# Crawler_Power_V2_0.net
KiCad netlist of a schematic drawn in Altium Designer
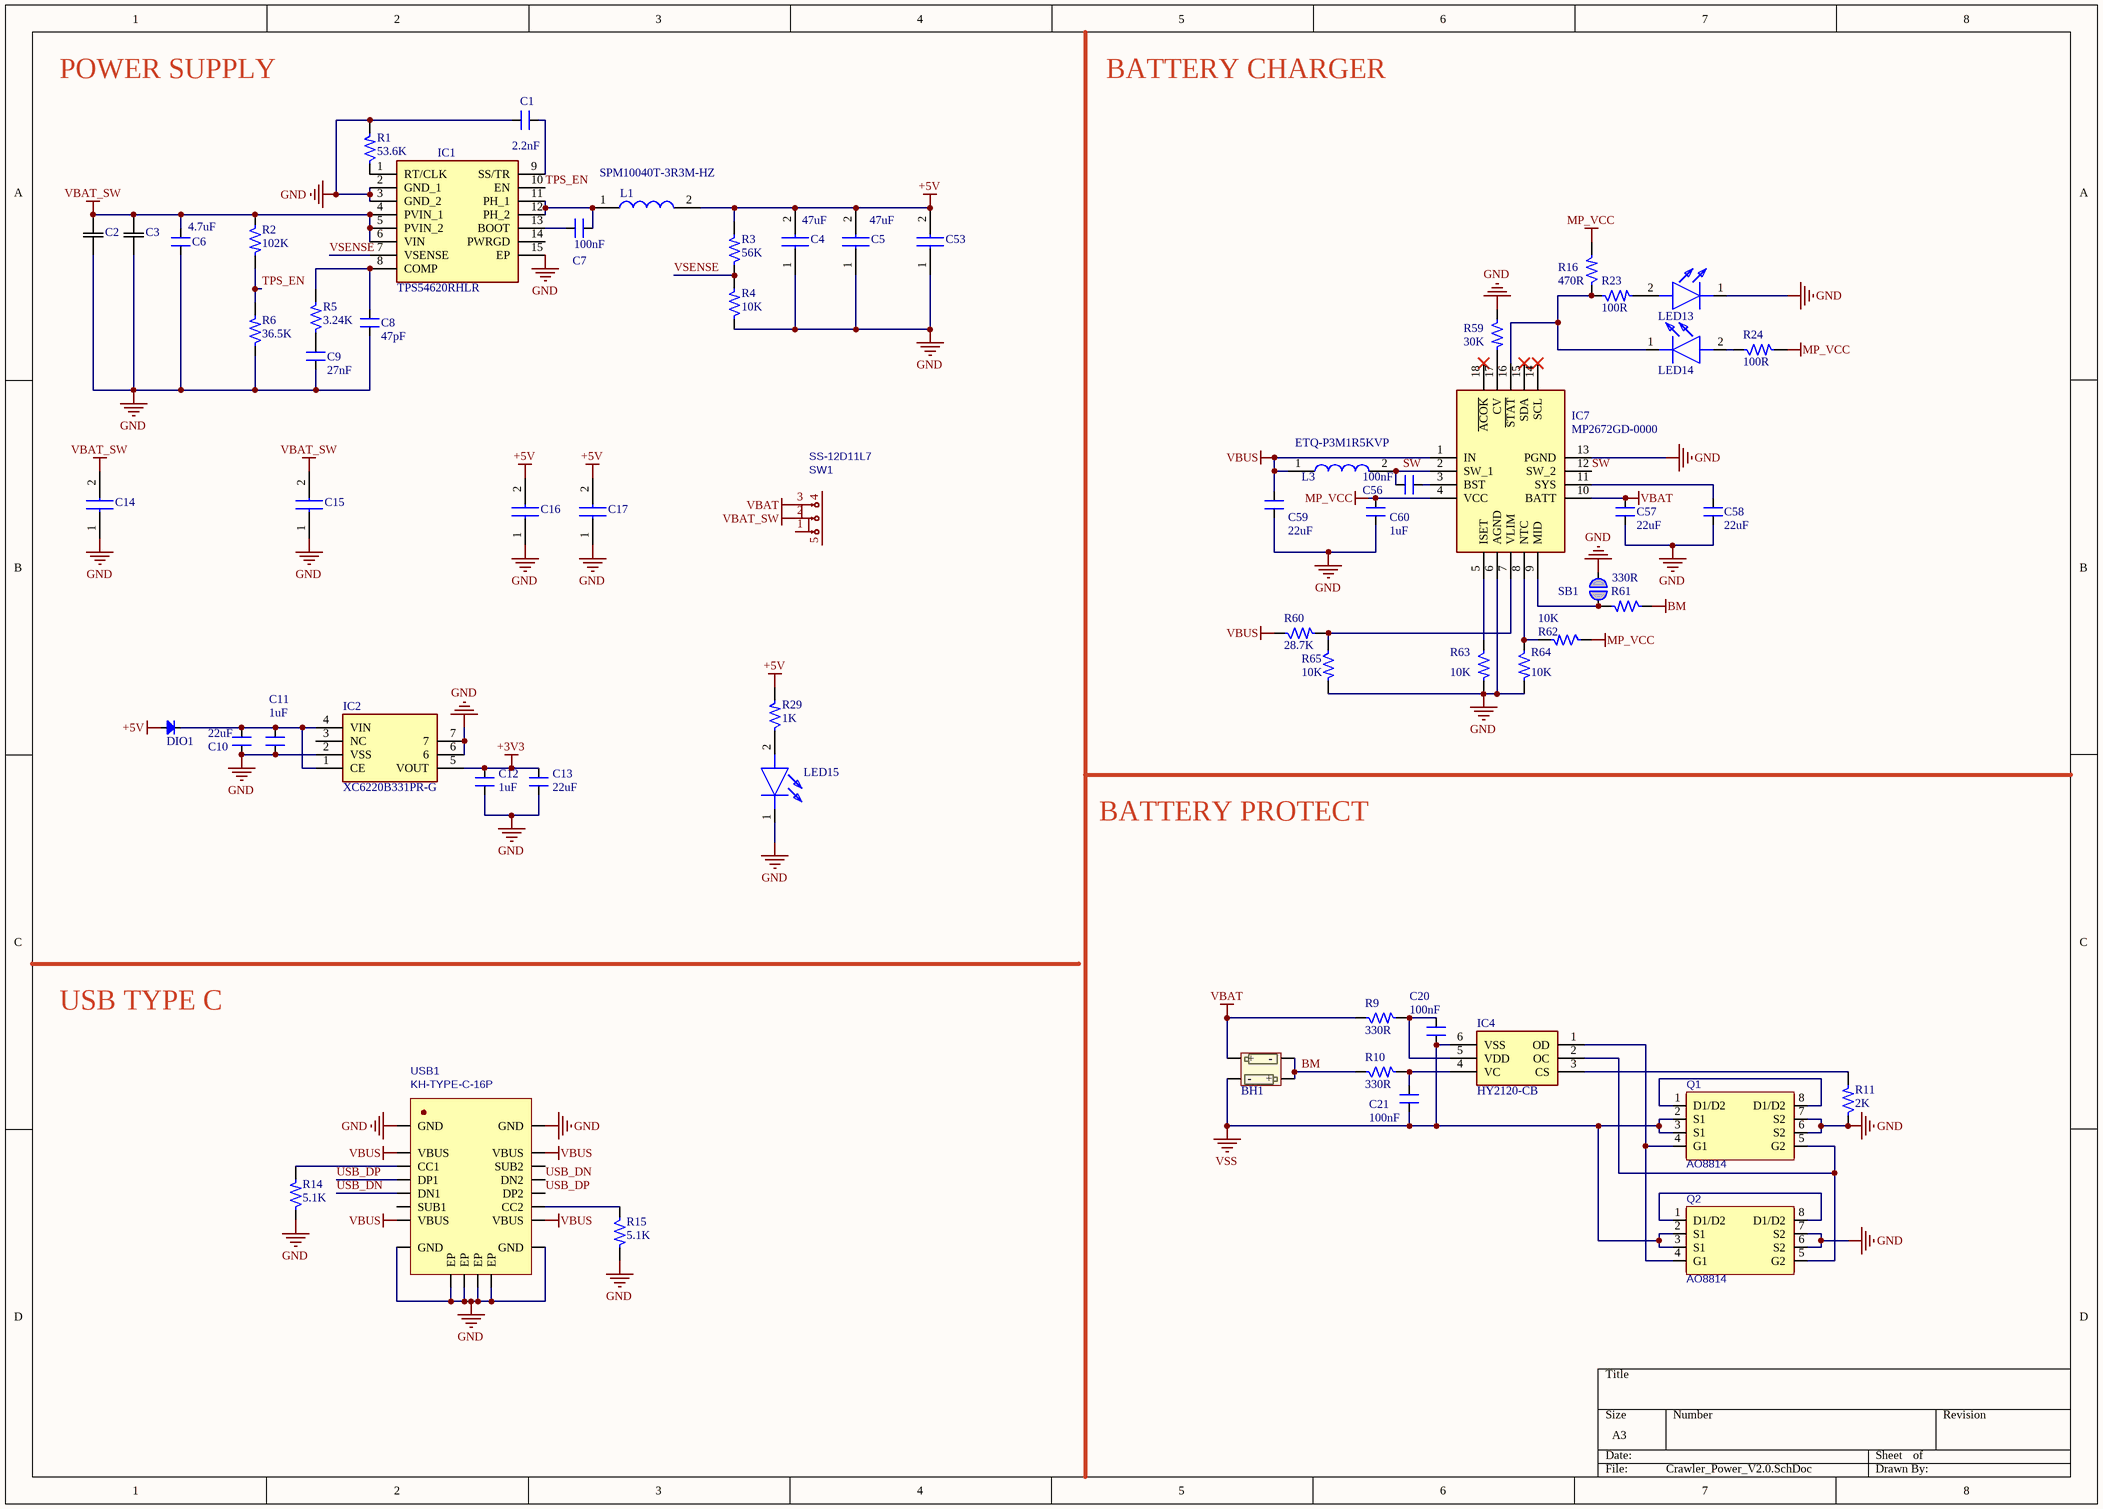
[diagram p0: Crawler_Power_V2.0.SchDoc]

(export (version "E")
  (design (tool "Eeschema 10.0.6"))
  (components
    (comp (ref "BH1")
      (value "Battery Holder")
      (footprint "BH-18650-B1BA007")
      (libsource (lib "SamacSys") (part "BH-18650-B1BA007"))
    )
    (comp (ref "C1")
      (value "2.2nF")
      (footprint "CAP_0402")
      (description "2.2nF ±10% 50V Ceramic Capacitor X7R 0402 (1005 Metric)")
      (fields
        (field (name "MANUFACTURER") "KEMET")
        (field (name "MANUFACTURER PART NUMBER") "C0402C221K8RAC7867")
      )
      (libsource (lib "EsteemPCB_SOM_Course_schlib") (part "CAP_220pF-10V-10%-0402"))
    )
    (comp (ref "C2")
      (value "CC1206MKX5R7BB106")
      (footprint "CAP_CC1206_YAG-M")
      (description "No Description Available")
      (fields (field (name "COPYRIGHT") "Copyright (C) 2023 Ultra Librarian. All rights reserved."))
      (libsource (lib "SamacSys") (part "CC1206MKX5R7BB106"))
    )
    (comp (ref "C3")
      (value "CC1206MKX5R7BB106")
      (footprint "CAP_CC1206_YAG-M")
      (description "No Description Available")
      (fields (field (name "COPYRIGHT") "Copyright (C) 2023 Ultra Librarian. All rights reserved."))
      (libsource (lib "SamacSys") (part "CC1206MKX5R7BB106"))
    )
    (comp (ref "C4")
      (value "GRM32ER61C476KE15L")
      (footprint "CAPC3225X270N")
      (description "Capacitor")
      (fields (field (name "MOUSER PART NUMBER") "81-GRM32ER61C476KE5L"))
      (libsource (lib "SamacSys") (part "GRM32ER61C476KE15L"))
    )
    (comp (ref "C5")
      (value "GRM32ER61C476KE15L")
      (footprint "CAPC3225X270N")
      (description "Capacitor")
      (fields (field (name "MOUSER PART NUMBER") "81-GRM32ER61C476KE5L"))
      (libsource (lib "SamacSys") (part "GRM32ER61C476KE15L"))
    )
    (comp (ref "C6")
      (value "4.7uF")
      (footprint "CAP_0402")
      (description "4.7µF ±10% 10V Ceramic Capacitor X5R 0402 (1005 Metric)")
      (fields
        (field (name "MANUFACTURER") "Samsung Electro-Mechanics")
        (field (name "MANUFACTURER PART NUMBER") "CL05A475KP5NRNC")
      )
      (libsource (lib "EsteemPCB_SOM_Course_schlib") (part "CAP_4.7uF-10V-10%-0402"))
    )
    (comp (ref "C7")
      (value "100nF")
      (footprint "CAP_0603")
      (description "25V 100nF X7R ±10% 0603 Multilayer Ceramic Capacitors MLCC - SMD/SMT ROHS")
      (fields
        (field (name "MANUFACTURER") "Yageo")
        (field (name "MANUFACTURER PART NUMBER") "CC0603KRX7R6BB104")
      )
      (libsource (lib "EsteemPCB_SOM_Course_schlib") (part "CAP_100nF-10V-5%-0603"))
    )
    (comp (ref "C8")
      (value "47pF")
      (footprint "CAP_0402")
      (description "82pF ±10% 50V Ceramic Capacitor NP0 0402 (1005 Metric)")
      (fields
        (field (name "MANUFACTURER") "KEMET")
        (field (name "MANUFACTURER PART NUMBER") "C0402C221K8RAC7867")
      )
      (libsource (lib "EsteemPCB_SOM_Course_schlib") (part "CAP_220pF-10V-10%-0402"))
    )
    (comp (ref "C9")
      (value "27nF")
      (footprint "CAP_0402")
      (description "27nF ±10% 50V Ceramic Capacitor X7R 0402 (1005 Metric)")
      (fields
        (field (name "MANUFACTURER") "KEMET")
        (field (name "MANUFACTURER PART NUMBER") "C0402C221K8RAC7867")
      )
      (libsource (lib "EsteemPCB_SOM_Course_schlib") (part "CAP_220pF-10V-10%-0402"))
    )
    (comp (ref "C10")
      (value "22uF")
      (footprint "CAP_0603")
      (description "22µF ±20% 10V Ceramic Capacitor X5R 0603 (1608 Metric)")
      (fields
        (field (name "MANUFACTURER") "Murata Electronics")
        (field (name "MANUFACTURER PART NUMBER") "GRM188R61A226ME15D")
      )
      (libsource (lib "EsteemPCB_SOM_Course_schlib") (part "CAP_22uF-10V-20%-0603"))
    )
    (comp (ref "C11")
      (value "1uF")
      (footprint "CAP_0402")
      (description "1µF ±10% 10V Ceramic Capacitor X6S 0402 (1005 Metric)")
      (fields
        (field (name "MANUFACTURER") "Murata Electronics")
        (field (name "MANUFACTURER PART NUMBER") "GRT155C81A105KE01D")
      )
      (libsource (lib "EsteemPCB_SOM_Course_schlib") (part "CAP_1uF-10V-10%-0402"))
    )
    (comp (ref "C12")
      (value "1uF")
      (footprint "CAP_0402")
      (description "1µF ±10% 10V Ceramic Capacitor X6S 0402 (1005 Metric)")
      (fields
        (field (name "MANUFACTURER") "Murata Electronics")
        (field (name "MANUFACTURER PART NUMBER") "GRT155C81A105KE01D")
      )
      (libsource (lib "EsteemPCB_SOM_Course_schlib") (part "CAP_1uF-10V-10%-0402"))
    )
    (comp (ref "C13")
      (value "22uF")
      (footprint "CAP_0603")
      (description "22µF ±20% 10V Ceramic Capacitor X5R 0603 (1608 Metric)")
      (fields
        (field (name "MANUFACTURER") "Murata Electronics")
        (field (name "MANUFACTURER PART NUMBER") "GRM188R61A226ME15D")
      )
      (libsource (lib "EsteemPCB_SOM_Course_schlib") (part "CAP_22uF-10V-20%-0603"))
    )
    (comp (ref "C14")
      (value "GRM32ER61C476KE15L")
      (footprint "CAPC3225X270N")
      (description "Capacitor")
      (fields (field (name "MOUSER PART NUMBER") "81-GRM32ER61C476KE5L"))
      (libsource (lib "SamacSys") (part "GRM32ER61C476KE15L"))
    )
    (comp (ref "C15")
      (value "GRM32ER61C476KE15L")
      (footprint "CAPC3225X270N")
      (description "Capacitor")
      (fields (field (name "MOUSER PART NUMBER") "81-GRM32ER61C476KE5L"))
      (libsource (lib "SamacSys") (part "GRM32ER61C476KE15L"))
    )
    (comp (ref "C16")
      (value "GRM32ER61C476KE15L")
      (footprint "CAPC3225X270N")
      (description "Capacitor")
      (fields (field (name "MOUSER PART NUMBER") "81-GRM32ER61C476KE5L"))
      (libsource (lib "SamacSys") (part "GRM32ER61C476KE15L"))
    )
    (comp (ref "C17")
      (value "GRM32ER61C476KE15L")
      (footprint "CAPC3225X270N")
      (description "Capacitor")
      (fields (field (name "MOUSER PART NUMBER") "81-GRM32ER61C476KE5L"))
      (libsource (lib "SamacSys") (part "GRM32ER61C476KE15L"))
    )
    (comp (ref "C20")
      (value "100nF")
      (footprint "CAP_0402")
      (description "0.1µF ±10% 25V Ceramic Capacitor X7R 0402 (1005 Metric)")
      (fields
        (field (name "MANUFACTURER") "Walsin Technology Corporation")
        (field (name "MANUFACTURER PART NUMBER") "0402B104K250CT")
      )
      (libsource (lib "EsteemPCB_SOM_Course_schlib") (part "CAP_100nF-25V-10%-0402"))
    )
    (comp (ref "C21")
      (value "100nF")
      (footprint "CAP_0402")
      (description "0.1µF ±10% 25V Ceramic Capacitor X7R 0402 (1005 Metric)")
      (fields
        (field (name "MANUFACTURER") "Walsin Technology Corporation")
        (field (name "MANUFACTURER PART NUMBER") "0402B104K250CT")
      )
      (libsource (lib "EsteemPCB_SOM_Course_schlib") (part "CAP_100nF-25V-10%-0402"))
    )
    (comp (ref "C53")
      (value "GRM32ER61C476KE15L")
      (footprint "CAPC3225X270N")
      (description "Capacitor")
      (fields (field (name "MOUSER PART NUMBER") "81-GRM32ER61C476KE5L"))
      (libsource (lib "SamacSys") (part "GRM32ER61C476KE15L"))
    )
    (comp (ref "C56")
      (value "100nF")
      (footprint "CAP_0603")
      (description "25V 100nF X7R ±10% 0603 Multilayer Ceramic Capacitors MLCC - SMD/SMT ROHS")
      (fields
        (field (name "MANUFACTURER") "Yageo")
        (field (name "MANUFACTURER PART NUMBER") "CC0603KRX7R6BB104")
      )
      (libsource (lib "EsteemPCB_SOM_Course_schlib") (part "CAP_100nF-10V-5%-0603"))
    )
    (comp (ref "C57")
      (value "22uF")
      (footprint "CAP_0805")
      (description "22µF ±20% 25V Ceramic Capacitor X5R 0805 (2012 Metric)")
      (fields
        (field (name "MANUFACTURER") "Murata Electronics")
        (field (name "MANUFACTURER PART NUMBER") "GRM21BR61E226ME44K")
      )
      (libsource (lib "EsteemPCB_SOM_Course_schlib") (part "CAP_22uF-25V-20%-0805"))
    )
    (comp (ref "C58")
      (value "22uF")
      (footprint "CAP_0805")
      (description "22µF ±20% 25V Ceramic Capacitor X5R 0805 (2012 Metric)")
      (fields
        (field (name "MANUFACTURER") "Murata Electronics")
        (field (name "MANUFACTURER PART NUMBER") "GRM21BR61E226ME44K")
      )
      (libsource (lib "EsteemPCB_SOM_Course_schlib") (part "CAP_22uF-25V-20%-0805"))
    )
    (comp (ref "C59")
      (value "22uF")
      (footprint "CAP_0603")
      (description "22µF ±20% 10V Ceramic Capacitor X5R 0603 (1608 Metric)")
      (fields
        (field (name "MANUFACTURER") "Murata Electronics")
        (field (name "MANUFACTURER PART NUMBER") "GRM188R61A226ME15D")
      )
      (libsource (lib "EsteemPCB_SOM_Course_schlib") (part "CAP_22uF-10V-20%-0603"))
    )
    (comp (ref "C60")
      (value "1uF")
      (footprint "CAP_0402")
      (description "1µF ±10% 10V Ceramic Capacitor X6S 0402 (1005 Metric)")
      (fields
        (field (name "MANUFACTURER") "Murata Electronics")
        (field (name "MANUFACTURER PART NUMBER") "GRT155C81A105KE01D")
      )
      (libsource (lib "EsteemPCB_SOM_Course_schlib") (part "CAP_1uF-10V-10%-0402"))
    )
    (comp (ref "DIO1")
      (value "Diode SMD")
      (footprint "DIO-SMD-123")
      (description "Default Diode")
      (fields (field (name "PUBLISHER") "Altium Limited"))
      (libsource (lib "LIBRARY") (part "Diode SMD"))
    )
    (comp (ref "IC1")
      (value "TPS54620RHLR")
      (footprint "SamacSys:TPS54622RHLR")
      (description "Integrated Circuit")
      (fields (field (name "MOUSER PART NUMBER") "595-TPS54620RHLR"))
      (libsource (lib "*") (part "TPS54620RHLR"))
    )
    (comp (ref "IC2")
      (value "XC6220B331PR-G")
      (footprint "XC6220B331PRG")
      (description "Integrated Circuit")
      (fields (field (name "MOUSER PART NUMBER") "865-XC6220B331PR-G"))
      (libsource (lib "*") (part "XC6220B331PR-G"))
    )
    (comp (ref "IC4")
      (value "HY2120-CB")
      (footprint "SamacSys:SOT95P280X140-6N")
      (description "Integrated Circuit")
      (libsource (lib "*") (part "HY2120-CB"))
    )
    (comp (ref "IC7")
      (value "MP2672GD-0000")
      (footprint "SamacSys:QFN40P200X300X100-18N-D")
      (description "Integrated Circuit")
      (libsource (lib "*") (part "MP2672GD-0000"))
    )
    (comp (ref "L1")
      (value "SPM10040T-3R3M-HZ")
      (footprint "SPM10040")
      (description "Inductor")
      (fields (field (name "MOUSER PART NUMBER") "810-SPM10040T-3R3HZ"))
      (libsource (lib "*") (part "SPM10040T-3R3M-HZ"))
    )
    (comp (ref "L3")
      (value "ETQ-P3M1R5KVP")
      (footprint "SamacSys:ETQ-P3M_KVP")
      (description "Inductor")
      (fields (field (name "MOUSER PART NUMBER") "667-ETQ-P3M1R5KVP"))
      (libsource (lib "*") (part "ETQ-P3M1R5KVP"))
    )
    (comp (ref "LED13")
      (value "LTST-C191KGKT")
      (footprint "SamacSys:LEDC1608X55N")
      (description "LED GREEN")
      (fields (field (name "MOUSER PART NUMBER") "859-LTST-C191KGKT"))
      (libsource (lib "SamacSys") (part "LTST-C191KGKT"))
    )
    (comp (ref "LED14")
      (value "LTST-C190KRKT")
      (footprint "LEDC1608X80N")
      (description "LED RED")
      (fields (field (name "MOUSER PART NUMBER") "859-LTST-C190KRKT"))
      (libsource (lib "SamacSys") (part "LTST-C190KRKT"))
    )
    (comp (ref "LED15")
      (value "LTST-C191KGKT")
      (footprint "SamacSys:LEDC1608X55N")
      (description "LED GREEN")
      (fields (field (name "MOUSER PART NUMBER") "859-LTST-C191KGKT"))
      (libsource (lib "SamacSys") (part "LTST-C191KGKT"))
    )
    (comp (ref "Q1")
      (value "AO8814")
      (footprint "TSSOP-8_L4.4-W3.0-P0.65-LS6.4-BL")
      (fields (field (name "BOM_SUPPLIER PART") "C357843") (field (name "CONTRIBUTOR") "LCSC"))
      (libsource (lib "SamacSys") (part "AO8814"))
    )
    (comp (ref "Q2")
      (value "AO8814")
      (footprint "TSSOP-8_L4.4-W3.0-P0.65-LS6.4-BL")
      (fields (field (name "BOM_SUPPLIER PART") "C357843") (field (name "CONTRIBUTOR") "LCSC"))
      (libsource (lib "SamacSys") (part "AO8814"))
    )
    (comp (ref "R1")
      (value "53.6K")
      (footprint "RES_0402")
      (description "53.6 kOhms ±1% 0.1W, 1/10W Chip Resistor 0402 (1005 Metric) Automotive AEC-Q200 Thick Film")
      (fields
        (field (name "MANUFACTURER") "Panasonic Electronic Components")
        (field (name "MANUFACTURER PART NUMBER") "ERJ-2RKF3003X")
      )
      (libsource (lib "EsteemPCB_SOM_Course_schlib") (part "RES_300K-0.1W-1%-0402"))
    )
    (comp (ref "R2")
      (value "102K")
      (footprint "RES_0402")
      (description "102 kOhms ±1% 0.1W, 1/10W Chip Resistor 0402 (1005 Metric) Automotive AEC-Q200 Thick Film")
      (fields
        (field (name "MANUFACTURER") "Panasonic Electronic Components")
        (field (name "MANUFACTURER PART NUMBER") "ERJ-2RKF3003X")
      )
      (libsource (lib "EsteemPCB_SOM_Course_schlib") (part "RES_300K-0.1W-1%-0402"))
    )
    (comp (ref "R3")
      (value "56K")
      (footprint "RES_0402")
      (description "56 kOhms ±1% 0.1W, 1/10W Chip Resistor 0402 (1005 Metric) Automotive AEC-Q200 Thick Film")
      (fields
        (field (name "MANUFACTURER") "Panasonic Electronic Components")
        (field (name "MANUFACTURER PART NUMBER") "ERJ-2RKF5102X")
      )
      (libsource (lib "EsteemPCB_SOM_Course_schlib") (part "RES_51K-0.1W-1%-0402"))
    )
    (comp (ref "R4")
      (value "10K")
      (footprint "RES_0402")
      (description "10 kOhms ±1% 0.1W, 1/10W Chip Resistor 0402 (1005 Metric) Anti-Sulfur Thin Film")
      (fields
        (field (name "MANUFACTURER") "Vishay Beyschlag/Draloric/BC Components")
        (field (name "MANUFACTURER PART NUMBER") "MCS04020C1002FE000")
      )
      (libsource (lib "EsteemPCB_SOM_Course_schlib") (part "RES_10K-0.1W-1%-0402"))
    )
    (comp (ref "R5")
      (value "3.24K")
      (footprint "RES_0402")
      (description "3.24 kOhms ±1% 0.1W, 1/10W Chip Resistor 0402 (1005 Metric) Automotive AEC-Q200 Thick Film")
      (fields
        (field (name "MANUFACTURER") "Panasonic Electronic Components")
        (field (name "MANUFACTURER PART NUMBER") "ERJ-2RKF3003X")
      )
      (libsource (lib "EsteemPCB_SOM_Course_schlib") (part "RES_300K-0.1W-1%-0402"))
    )
    (comp (ref "R6")
      (value "36.5K")
      (footprint "RES_0402")
      (description "28.7 kOhms ±1% 0.1W, 1/10W Chip Resistor 0402 (1005 Metric) Automotive AEC-Q200 Thick Film")
      (fields
        (field (name "MANUFACTURER") "Panasonic Electronic Components")
        (field (name "MANUFACTURER PART NUMBER") "ERJ-2RKF3003X")
      )
      (libsource (lib "EsteemPCB_SOM_Course_schlib") (part "RES_300K-0.1W-1%-0402"))
    )
    (comp (ref "R9")
      (value "330R")
      (footprint "RES_0402")
      (description "330 Ohms ±1% 0.1W, 1/10W Chip Resistor 0402 (1005 Metric) Automotive AEC-Q200 Thick Film")
      (fields
        (field (name "MANUFACTURER") "Panasonic Electronic Components")
        (field (name "MANUFACTURER PART NUMBER") "ERJ-2RKF3003X")
      )
      (libsource (lib "EsteemPCB_SOM_Course_schlib") (part "RES_300K-0.1W-1%-0402"))
    )
    (comp (ref "R10")
      (value "330R")
      (footprint "RES_0402")
      (description "330 Ohms ±1% 0.1W, 1/10W Chip Resistor 0402 (1005 Metric) Automotive AEC-Q200 Thick Film")
      (fields
        (field (name "MANUFACTURER") "Panasonic Electronic Components")
        (field (name "MANUFACTURER PART NUMBER") "ERJ-2RKF3003X")
      )
      (libsource (lib "EsteemPCB_SOM_Course_schlib") (part "RES_300K-0.1W-1%-0402"))
    )
    (comp (ref "R11")
      (value "2K")
      (footprint "RES_0402")
      (description "2 kOhms ±1% 0.1W, 1/10W Chip Resistor 0402 (1005 Metric) Automotive AEC-Q200 Thick Film")
      (fields
        (field (name "MANUFACTURER") "Panasonic Electronic Components")
        (field (name "MANUFACTURER PART NUMBER") "ERJ-2RKF2003X")
      )
      (libsource (lib "EsteemPCB_SOM_Course_schlib") (part "RES_200K-0.1W-1%-0402"))
    )
    (comp (ref "R14")
      (value "5.1K")
      (footprint "RES_0402")
      (fields
        (field (name "MANUFACTURER") "KOA Speer Electronics, Inc.")
        (field (name "MANUFACTURER PART NUMBER") "RK73H1ETTP5601F")
      )
      (libsource (lib "EsteemPCB_SOM_Course_schlib") (part "RES_5.6K-0.1W-1%-0402"))
    )
    (comp (ref "R15")
      (value "5.1K")
      (footprint "RES_0402")
      (fields
        (field (name "MANUFACTURER") "KOA Speer Electronics, Inc.")
        (field (name "MANUFACTURER PART NUMBER") "RK73H1ETTP5601F")
      )
      (libsource (lib "EsteemPCB_SOM_Course_schlib") (part "RES_5.6K-0.1W-1%-0402"))
    )
    (comp (ref "R16")
      (value "470R")
      (footprint "RES_0402")
      (fields
        (field (name "MANUFACTURER") "KOA Speer Electronics, Inc.")
        (field (name "MANUFACTURER PART NUMBER") "RK73H1ETTP1000F")
      )
      (libsource (lib "EsteemPCB_SOM_Course_schlib") (part "RES_100R-0.1W-1%-0402"))
    )
    (comp (ref "R23")
      (value "100R")
      (footprint "RES_0402")
      (fields
        (field (name "MANUFACTURER") "KOA Speer Electronics, Inc.")
        (field (name "MANUFACTURER PART NUMBER") "RK73H1ETTP1000F")
      )
      (libsource (lib "EsteemPCB_SOM_Course_schlib") (part "RES_100R-0.1W-1%-0402"))
    )
    (comp (ref "R24")
      (value "100R")
      (footprint "RES_0402")
      (fields
        (field (name "MANUFACTURER") "KOA Speer Electronics, Inc.")
        (field (name "MANUFACTURER PART NUMBER") "RK73H1ETTP1000F")
      )
      (libsource (lib "EsteemPCB_SOM_Course_schlib") (part "RES_100R-0.1W-1%-0402"))
    )
    (comp (ref "R29")
      (value "1K")
      (footprint "RES_0402")
      (description "1 kOhms ±1% 0.1W, 1/10W Chip Resistor 0402 (1005 Metric) Anti-Sulfur Thin Film")
      (fields
        (field (name "MANUFACTURER") "Vishay Beyschlag/Draloric/BC Components")
        (field (name "MANUFACTURER PART NUMBER") "MCS04020C1001FE000")
      )
      (libsource (lib "EsteemPCB_SOM_Course_schlib") (part "RES_1K-0.1W-1%-0402"))
    )
    (comp (ref "R59")
      (value "30K")
      (footprint "RES_0402")
      (description "30 kOhms ±1% 0.1W, 1/10W Chip Resistor 0402 (1005 Metric) Anti-Sulfur Thin Film")
      (fields
        (field (name "MANUFACTURER") "Vishay Beyschlag/Draloric/BC Components")
        (field (name "MANUFACTURER PART NUMBER") "MCS04020C1002FE000")
      )
      (libsource (lib "EsteemPCB_SOM_Course_schlib") (part "RES_10K-0.1W-1%-0402"))
    )
    (comp (ref "R60")
      (value "28.7K")
      (footprint "RES_0402")
      (description "28.7 kOhms ±1% 0.1W, 1/10W Chip Resistor 0402 (1005 Metric) Anti-Sulfur Thin Film")
      (fields
        (field (name "MANUFACTURER") "Vishay Beyschlag/Draloric/BC Components")
        (field (name "MANUFACTURER PART NUMBER") "MCS04020C1002FE000")
      )
      (libsource (lib "EsteemPCB_SOM_Course_schlib") (part "RES_10K-0.1W-1%-0402"))
    )
    (comp (ref "R61")
      (value "330R")
      (footprint "RES_0402")
      (description "330 Ohms ±1% 0.1W, 1/10W Chip Resistor 0402 (1005 Metric) Automotive AEC-Q200 Thick Film")
      (fields
        (field (name "MANUFACTURER") "Panasonic Electronic Components")
        (field (name "MANUFACTURER PART NUMBER") "ERJ-2RKF3003X")
      )
      (libsource (lib "EsteemPCB_SOM_Course_schlib") (part "RES_300K-0.1W-1%-0402"))
    )
    (comp (ref "R62")
      (value "10K")
      (footprint "RES_0402")
      (description "10 kOhms ±1% 0.1W, 1/10W Chip Resistor 0402 (1005 Metric) Anti-Sulfur Thin Film")
      (fields
        (field (name "MANUFACTURER") "Vishay Beyschlag/Draloric/BC Components")
        (field (name "MANUFACTURER PART NUMBER") "MCS04020C1002FE000")
      )
      (libsource (lib "EsteemPCB_SOM_Course_schlib") (part "RES_10K-0.1W-1%-0402"))
    )
    (comp (ref "R63")
      (value "10K")
      (footprint "RES_0402")
      (description "10 kOhms ±1% 0.1W, 1/10W Chip Resistor 0402 (1005 Metric) Anti-Sulfur Thin Film")
      (fields
        (field (name "MANUFACTURER") "Vishay Beyschlag/Draloric/BC Components")
        (field (name "MANUFACTURER PART NUMBER") "MCS04020C1002FE000")
      )
      (libsource (lib "EsteemPCB_SOM_Course_schlib") (part "RES_10K-0.1W-1%-0402"))
    )
    (comp (ref "R64")
      (value "10K")
      (footprint "RES_0402")
      (description "10 kOhms ±1% 0.1W, 1/10W Chip Resistor 0402 (1005 Metric) Anti-Sulfur Thin Film")
      (fields
        (field (name "MANUFACTURER") "Vishay Beyschlag/Draloric/BC Components")
        (field (name "MANUFACTURER PART NUMBER") "MCS04020C1002FE000")
      )
      (libsource (lib "EsteemPCB_SOM_Course_schlib") (part "RES_10K-0.1W-1%-0402"))
    )
    (comp (ref "R65")
      (value "10K")
      (footprint "RES_0402")
      (description "10 kOhms ±1% 0.1W, 1/10W Chip Resistor 0402 (1005 Metric) Anti-Sulfur Thin Film")
      (fields
        (field (name "MANUFACTURER") "Vishay Beyschlag/Draloric/BC Components")
        (field (name "MANUFACTURER PART NUMBER") "MCS04020C1002FE000")
      )
      (libsource (lib "EsteemPCB_SOM_Course_schlib") (part "RES_10K-0.1W-1%-0402"))
    )
    (comp (ref "SB1")
      (value "Solderbridge")
      (footprint "Solderbridge")
      (fields (field (name "PUBLISHER") "Nordic Semiconductor"))
      (libsource (lib "SamacSys") (part "SOLDERBRIDGE"))
    )
    (comp (ref "SW1")
      (value "SS-12D11L7")
      (footprint "SW-TH_XKB_SS-12D11L7")
      (fields (field (name "BOM_SUPPLIER PART") "C2884775") (field (name "CONTRIBUTOR") "LCSC"))
      (libsource (lib "SamacSys") (part "SS-12D11L7"))
    )
    (comp (ref "USB1")
      (value "KH-TYPE-C-16P")
      (footprint "USB-C-SMD_KH-TYPE-C-16P")
      (fields (field (name "BOM_SUPPLIER PART") "C709357") (field (name "CONTRIBUTOR") "LCSC"))
      (libsource (lib "SamacSys") (part "KH-TYPE-C-16P"))
    )
  )
  (nets
    (net (code "1") (name "+3V3") (class "Default")
      (node (ref "C12") (pin "2") (pinfunction "2_2") (pintype "passive"))
      (node (ref "C13") (pin "2") (pinfunction "2_2") (pintype "passive"))
      (node (ref "IC2") (pin "5") (pinfunction "VOUT_5") (pintype "passive"))
    )
    (net (code "2") (name "+5V") (class "Default")
      (node (ref "C16") (pin "2") (pinfunction "2_2") (pintype "passive"))
      (node (ref "C17") (pin "2") (pinfunction "2_2") (pintype "passive"))
      (node (ref "C4") (pin "2") (pinfunction "2_2") (pintype "passive"))
      (node (ref "C5") (pin "2") (pinfunction "2_2") (pintype "passive"))
      (node (ref "C53") (pin "2") (pinfunction "2_2") (pintype "passive"))
      (node (ref "DIO1") (pin "1") (pinfunction "A_1") (pintype "passive"))
      (node (ref "L1") (pin "2") (pinfunction "2_2") (pintype "passive"))
      (node (ref "R29") (pin "2") (pinfunction "2_2") (pintype "passive"))
      (node (ref "R3") (pin "2") (pinfunction "2_2") (pintype "passive"))
    )
    (net (code "3") (name "/SW") (class "Default")
      (node (ref "C56") (pin "1") (pinfunction "1_1") (pintype "passive"))
      (node (ref "IC7") (pin "12") (pinfunction "SW_2_12") (pintype "passive"))
      (node (ref "IC7") (pin "2") (pinfunction "SW_1_2") (pintype "passive"))
      (node (ref "L3") (pin "2") (pinfunction "2_2") (pintype "passive"))
    )
    (net (code "4") (name "/TPS_EN") (class "Default")
      (node (ref "IC1") (pin "10") (pinfunction "EN_10") (pintype "passive"))
      (node (ref "R2") (pin "2") (pinfunction "2_2") (pintype "passive"))
      (node (ref "R6") (pin "2") (pinfunction "2_2") (pintype "passive"))
    )
    (net (code "5") (name "/USB_DN") (class "Default")
      (node (ref "USB1") (pin "A7") (pinfunction "DN1_A7") (pintype "passive"))
      (node (ref "USB1") (pin "B7") (pinfunction "DN2_B7") (pintype "passive"))
    )
    (net (code "6") (name "/USB_DP") (class "Default")
      (node (ref "USB1") (pin "A6") (pinfunction "DP1_A6") (pintype "passive"))
      (node (ref "USB1") (pin "B6") (pinfunction "DP2_B6") (pintype "passive"))
    )
    (net (code "7") (name "/VSENSE") (class "Default")
      (node (ref "IC1") (pin "7") (pinfunction "VSENSE_7") (pintype "passive"))
      (node (ref "R3") (pin "1") (pinfunction "1_1") (pintype "passive"))
      (node (ref "R4") (pin "2") (pinfunction "2_2") (pintype "passive"))
    )
    (net (code "8") (name "BM") (class "Default")
      (node (ref "BH1") (pin "2") (pinfunction "-_2") (pintype "passive"))
      (node (ref "BH1") (pin "4") (pinfunction "+_4") (pintype "passive"))
      (node (ref "R10") (pin "1") (pinfunction "1_1") (pintype "passive"))
      (node (ref "R61") (pin "1") (pinfunction "1_1") (pintype "passive"))
    )
    (net (code "9") (name "GND") (class "Default")
      (node (ref "C1") (pin "2") (pinfunction "2_2") (pintype "passive"))
      (node (ref "C10") (pin "1") (pinfunction "1_1") (pintype "passive"))
      (node (ref "C11") (pin "1") (pinfunction "1_1") (pintype "passive"))
      (node (ref "C12") (pin "1") (pinfunction "1_1") (pintype "passive"))
      (node (ref "C13") (pin "1") (pinfunction "1_1") (pintype "passive"))
      (node (ref "C14") (pin "1") (pinfunction "1_1") (pintype "passive"))
      (node (ref "C15") (pin "1") (pinfunction "1_1") (pintype "passive"))
      (node (ref "C16") (pin "1") (pinfunction "1_1") (pintype "passive"))
      (node (ref "C17") (pin "1") (pinfunction "1_1") (pintype "passive"))
      (node (ref "C2") (pin "1") (pinfunction "1_1") (pintype "passive"))
      (node (ref "C3") (pin "1") (pinfunction "1_1") (pintype "passive"))
      (node (ref "C4") (pin "1") (pinfunction "1_1") (pintype "passive"))
      (node (ref "C5") (pin "1") (pinfunction "1_1") (pintype "passive"))
      (node (ref "C53") (pin "1") (pinfunction "1_1") (pintype "passive"))
      (node (ref "C57") (pin "1") (pinfunction "1_1") (pintype "passive"))
      (node (ref "C58") (pin "1") (pinfunction "1_1") (pintype "passive"))
      (node (ref "C59") (pin "1") (pinfunction "1_1") (pintype "passive"))
      (node (ref "C6") (pin "1") (pinfunction "1_1") (pintype "passive"))
      (node (ref "C60") (pin "1") (pinfunction "1_1") (pintype "passive"))
      (node (ref "C8") (pin "1") (pinfunction "1_1") (pintype "passive"))
      (node (ref "C9") (pin "1") (pinfunction "1_1") (pintype "passive"))
      (node (ref "IC1") (pin "15") (pinfunction "EP_15") (pintype "passive"))
      (node (ref "IC1") (pin "2") (pinfunction "GND_1_2") (pintype "passive"))
      (node (ref "IC1") (pin "3") (pinfunction "GND_2_3") (pintype "passive"))
      (node (ref "IC2") (pin "2") (pinfunction "VSS_2") (pintype "passive"))
      (node (ref "IC2") (pin "6") (pinfunction "6_6") (pintype "passive"))
      (node (ref "IC2") (pin "7") (pinfunction "7_7") (pintype "passive"))
      (node (ref "IC7") (pin "13") (pinfunction "PGND_13") (pintype "passive"))
      (node (ref "IC7") (pin "6") (pinfunction "AGND_6") (pintype "passive"))
      (node (ref "LED13") (pin "1") (pinfunction "K_1") (pintype "passive"))
      (node (ref "LED15") (pin "1") (pinfunction "K_1") (pintype "passive"))
      (node (ref "Q1") (pin "6") (pinfunction "S2_6") (pintype "passive"))
      (node (ref "Q1") (pin "7") (pinfunction "S2_7") (pintype "passive"))
      (node (ref "Q2") (pin "6") (pinfunction "S2_6") (pintype "passive"))
      (node (ref "Q2") (pin "7") (pinfunction "S2_7") (pintype "passive"))
      (node (ref "R1") (pin "2") (pinfunction "2_2") (pintype "passive"))
      (node (ref "R11") (pin "1") (pinfunction "1_1") (pintype "passive"))
      (node (ref "R14") (pin "1") (pinfunction "1_1") (pintype "passive"))
      (node (ref "R15") (pin "2") (pinfunction "2_2") (pintype "passive"))
      (node (ref "R4") (pin "1") (pinfunction "1_1") (pintype "passive"))
      (node (ref "R59") (pin "1") (pinfunction "1_1") (pintype "passive"))
      (node (ref "R6") (pin "1") (pinfunction "1_1") (pintype "passive"))
      (node (ref "R63") (pin "2") (pinfunction "2_2") (pintype "passive"))
      (node (ref "R64") (pin "2") (pinfunction "2_2") (pintype "passive"))
      (node (ref "R65") (pin "2") (pinfunction "2_2") (pintype "passive"))
      (node (ref "SB1") (pin "2") (pinfunction "1_2") (pintype "passive"))
      (node (ref "USB1") (pin "1") (pinfunction "EP_1") (pintype "passive"))
      (node (ref "USB1") (pin "2") (pinfunction "EP_2") (pintype "passive"))
      (node (ref "USB1") (pin "3") (pinfunction "EP_3") (pintype "passive"))
      (node (ref "USB1") (pin "4") (pinfunction "EP_4") (pintype "passive"))
      (node (ref "USB1") (pin "A1") (pinfunction "GND_A1") (pintype "passive"))
      (node (ref "USB1") (pin "A12") (pinfunction "GND_A12") (pintype "passive"))
      (node (ref "USB1") (pin "B1") (pinfunction "GND_B1") (pintype "passive"))
      (node (ref "USB1") (pin "B12") (pinfunction "GND_B12") (pintype "passive"))
    )
    (net (code "10") (name "MP_VCC") (class "Default")
      (node (ref "C60") (pin "2") (pinfunction "2_2") (pintype "passive"))
      (node (ref "IC7") (pin "4") (pinfunction "VCC_4") (pintype "passive"))
      (node (ref "R16") (pin "2") (pinfunction "2_2") (pintype "passive"))
      (node (ref "R24") (pin "2") (pinfunction "2_2") (pintype "passive"))
      (node (ref "R62") (pin "1") (pinfunction "1_1") (pintype "passive"))
    )
    (net (code "11") (name "Net-(C9-Pad2)") (class "Default")
      (node (ref "C9") (pin "2") (pinfunction "2_2") (pintype "passive"))
      (node (ref "R5") (pin "1") (pinfunction "1_1") (pintype "passive"))
    )
    (net (code "12") (name "Net-(DIO1-K)") (class "Default")
      (node (ref "C10") (pin "2") (pinfunction "2_2") (pintype "passive"))
      (node (ref "C11") (pin "2") (pinfunction "2_2") (pintype "passive"))
      (node (ref "DIO1") (pin "2") (pinfunction "K_2") (pintype "passive"))
      (node (ref "IC2") (pin "1") (pinfunction "CE_1") (pintype "passive"))
      (node (ref "IC2") (pin "4") (pinfunction "VIN_4") (pintype "passive"))
    )
    (net (code "13") (name "Net-(IC1-BOOT)") (class "Default")
      (node (ref "C7") (pin "1") (pinfunction "1_1") (pintype "passive"))
      (node (ref "IC1") (pin "13") (pinfunction "BOOT_13") (pintype "passive"))
    )
    (net (code "14") (name "Net-(IC1-COMP)") (class "Default")
      (node (ref "C8") (pin "2") (pinfunction "2_2") (pintype "passive"))
      (node (ref "IC1") (pin "8") (pinfunction "COMP_8") (pintype "passive"))
      (node (ref "R5") (pin "2") (pinfunction "2_2") (pintype "passive"))
    )
    (net (code "15") (name "Net-(IC1-PH_1)") (class "Default")
      (node (ref "C7") (pin "2") (pinfunction "2_2") (pintype "passive"))
      (node (ref "IC1") (pin "11") (pinfunction "PH_1_11") (pintype "passive"))
      (node (ref "IC1") (pin "12") (pinfunction "PH_2_12") (pintype "passive"))
      (node (ref "L1") (pin "1") (pinfunction "1_1") (pintype "passive"))
    )
    (net (code "16") (name "Net-(IC1-RT{slash}CLK)") (class "Default")
      (node (ref "IC1") (pin "1") (pinfunction "RT/CLK_1") (pintype "passive"))
      (node (ref "R1") (pin "1") (pinfunction "1_1") (pintype "passive"))
    )
    (net (code "17") (name "Net-(IC1-SS{slash}TR)") (class "Default")
      (node (ref "C1") (pin "1") (pinfunction "1_1") (pintype "passive"))
      (node (ref "IC1") (pin "9") (pinfunction "SS/TR_9") (pintype "passive"))
    )
    (net (code "18") (name "Net-(IC4-CS)") (class "Default")
      (node (ref "IC4") (pin "3") (pinfunction "CS_3") (pintype "passive"))
      (node (ref "R11") (pin "2") (pinfunction "2_2") (pintype "passive"))
    )
    (net (code "19") (name "Net-(IC4-OC)") (class "Default")
      (node (ref "IC4") (pin "2") (pinfunction "OC_2") (pintype "passive"))
      (node (ref "Q1") (pin "5") (pinfunction "G2_5") (pintype "passive"))
      (node (ref "Q2") (pin "5") (pinfunction "G2_5") (pintype "passive"))
    )
    (net (code "20") (name "Net-(IC4-OD)") (class "Default")
      (node (ref "IC4") (pin "1") (pinfunction "OD_1") (pintype "passive"))
      (node (ref "Q1") (pin "4") (pinfunction "G1_4") (pintype "passive"))
      (node (ref "Q2") (pin "4") (pinfunction "G1_4") (pintype "passive"))
    )
    (net (code "21") (name "Net-(IC4-VC)") (class "Default")
      (node (ref "C21") (pin "2") (pinfunction "2_2") (pintype "passive"))
      (node (ref "IC4") (pin "4") (pinfunction "VC_4") (pintype "passive"))
      (node (ref "R10") (pin "2") (pinfunction "2_2") (pintype "passive"))
    )
    (net (code "22") (name "Net-(IC4-VDD)") (class "Default")
      (node (ref "C20") (pin "1") (pinfunction "1_1") (pintype "passive"))
      (node (ref "IC4") (pin "5") (pinfunction "VDD_5") (pintype "passive"))
      (node (ref "R9") (pin "2") (pinfunction "2_2") (pintype "passive"))
    )
    (net (code "23") (name "Net-(IC7-BST)") (class "Default")
      (node (ref "C56") (pin "2") (pinfunction "2_2") (pintype "passive"))
      (node (ref "IC7") (pin "3") (pinfunction "BST_3") (pintype "passive"))
    )
    (net (code "24") (name "Net-(IC7-CV)") (class "Default")
      (node (ref "IC7") (pin "17") (pinfunction "CV_17") (pintype "passive"))
      (node (ref "R59") (pin "2") (pinfunction "2_2") (pintype "passive"))
    )
    (net (code "25") (name "Net-(IC7-ISET)") (class "Default")
      (node (ref "IC7") (pin "5") (pinfunction "ISET_5") (pintype "passive"))
      (node (ref "R63") (pin "1") (pinfunction "1_1") (pintype "passive"))
    )
    (net (code "26") (name "Net-(IC7-MID)") (class "Default")
      (node (ref "IC7") (pin "9") (pinfunction "MID_9") (pintype "passive"))
      (node (ref "R61") (pin "2") (pinfunction "2_2") (pintype "passive"))
      (node (ref "SB1") (pin "1") (pinfunction "0_1") (pintype "passive"))
    )
    (net (code "27") (name "Net-(IC7-NTC)") (class "Default")
      (node (ref "IC7") (pin "8") (pinfunction "NTC_8") (pintype "passive"))
      (node (ref "R62") (pin "2") (pinfunction "2_2") (pintype "passive"))
      (node (ref "R64") (pin "1") (pinfunction "1_1") (pintype "passive"))
    )
    (net (code "28") (name "Net-(IC7-SYS)") (class "Default")
      (node (ref "C58") (pin "2") (pinfunction "2_2") (pintype "passive"))
      (node (ref "IC7") (pin "11") (pinfunction "SYS_11") (pintype "passive"))
    )
    (net (code "29") (name "Net-(IC7-VLIM)") (class "Default")
      (node (ref "IC7") (pin "7") (pinfunction "VLIM_7") (pintype "passive"))
      (node (ref "R60") (pin "2") (pinfunction "2_2") (pintype "passive"))
      (node (ref "R65") (pin "1") (pinfunction "1_1") (pintype "passive"))
    )
    (net (code "30") (name "Net-(IC7-~{STAT})") (class "Default")
      (node (ref "IC7") (pin "16") (pinfunction "~{STAT}_16") (pintype "passive"))
      (node (ref "LED14") (pin "1") (pinfunction "K_1") (pintype "passive"))
      (node (ref "R16") (pin "1") (pinfunction "1_1") (pintype "passive"))
      (node (ref "R23") (pin "1") (pinfunction "1_1") (pintype "passive"))
    )
    (net (code "31") (name "Net-(LED13-A)") (class "Default")
      (node (ref "LED13") (pin "2") (pinfunction "A_2") (pintype "passive"))
      (node (ref "R23") (pin "2") (pinfunction "2_2") (pintype "passive"))
    )
    (net (code "32") (name "Net-(LED14-A)") (class "Default")
      (node (ref "LED14") (pin "2") (pinfunction "A_2") (pintype "passive"))
      (node (ref "R24") (pin "1") (pinfunction "1_1") (pintype "passive"))
    )
    (net (code "33") (name "Net-(LED15-A)") (class "Default")
      (node (ref "LED15") (pin "2") (pinfunction "A_2") (pintype "passive"))
      (node (ref "R29") (pin "1") (pinfunction "1_1") (pintype "passive"))
    )
    (net (code "34") (name "Net-(Q1-D1{slash}D2-Pad1)") (class "Default")
      (node (ref "Q1") (pin "1") (pinfunction "D1/D2_1") (pintype "passive"))
      (node (ref "Q1") (pin "8") (pinfunction "D1/D2_8") (pintype "passive"))
    )
    (net (code "35") (name "Net-(Q2-D1{slash}D2-Pad1)") (class "Default")
      (node (ref "Q2") (pin "1") (pinfunction "D1/D2_1") (pintype "passive"))
      (node (ref "Q2") (pin "8") (pinfunction "D1/D2_8") (pintype "passive"))
    )
    (net (code "36") (name "Net-(USB1-CC1)") (class "Default")
      (node (ref "R14") (pin "2") (pinfunction "2_2") (pintype "passive"))
      (node (ref "USB1") (pin "A5") (pinfunction "CC1_A5") (pintype "passive"))
    )
    (net (code "37") (name "Net-(USB1-CC2)") (class "Default")
      (node (ref "R15") (pin "1") (pinfunction "1_1") (pintype "passive"))
      (node (ref "USB1") (pin "B5") (pinfunction "CC2_B5") (pintype "passive"))
    )
    (net (code "38") (name "VBAT") (class "Default")
      (node (ref "BH1") (pin "1") (pinfunction "+_1") (pintype "passive"))
      (node (ref "C57") (pin "2") (pinfunction "2_2") (pintype "passive"))
      (node (ref "IC7") (pin "10") (pinfunction "BATT_10") (pintype "passive"))
      (node (ref "R9") (pin "1") (pinfunction "1_1") (pintype "passive"))
      (node (ref "SW1") (pin "3") (pinfunction "3_3") (pintype "passive"))
    )
    (net (code "39") (name "VBAT_SW") (class "Default")
      (node (ref "C14") (pin "2") (pinfunction "2_2") (pintype "passive"))
      (node (ref "C15") (pin "2") (pinfunction "2_2") (pintype "passive"))
      (node (ref "C2") (pin "2") (pinfunction "2_2") (pintype "passive"))
      (node (ref "C3") (pin "2") (pinfunction "2_2") (pintype "passive"))
      (node (ref "C6") (pin "2") (pinfunction "2_2") (pintype "passive"))
      (node (ref "IC1") (pin "4") (pinfunction "PVIN_1_4") (pintype "passive"))
      (node (ref "IC1") (pin "5") (pinfunction "PVIN_2_5") (pintype "passive"))
      (node (ref "IC1") (pin "6") (pinfunction "VIN_6") (pintype "passive"))
      (node (ref "R2") (pin "1") (pinfunction "1_1") (pintype "passive"))
      (node (ref "SW1") (pin "2") (pinfunction "2_2") (pintype "passive"))
    )
    (net (code "40") (name "VBUS") (class "Default")
      (node (ref "C59") (pin "2") (pinfunction "2_2") (pintype "passive"))
      (node (ref "IC7") (pin "1") (pinfunction "IN_1") (pintype "passive"))
      (node (ref "L3") (pin "1") (pinfunction "1_1") (pintype "passive"))
      (node (ref "R60") (pin "1") (pinfunction "1_1") (pintype "passive"))
      (node (ref "USB1") (pin "A4") (pinfunction "VBUS_A4") (pintype "passive"))
      (node (ref "USB1") (pin "A9") (pinfunction "VBUS_A9") (pintype "passive"))
      (node (ref "USB1") (pin "B4") (pinfunction "VBUS_B4") (pintype "passive"))
      (node (ref "USB1") (pin "B9") (pinfunction "VBUS_B9") (pintype "passive"))
    )
    (net (code "41") (name "VSS") (class "Default")
      (node (ref "BH1") (pin "3") (pinfunction "-_3") (pintype "passive"))
      (node (ref "C20") (pin "2") (pinfunction "2_2") (pintype "passive"))
      (node (ref "C21") (pin "1") (pinfunction "1_1") (pintype "passive"))
      (node (ref "IC4") (pin "6") (pinfunction "VSS_6") (pintype "passive"))
      (node (ref "Q1") (pin "2") (pinfunction "S1_2") (pintype "passive"))
      (node (ref "Q1") (pin "3") (pinfunction "S1_3") (pintype "passive"))
      (node (ref "Q2") (pin "2") (pinfunction "S1_2") (pintype "passive"))
      (node (ref "Q2") (pin "3") (pinfunction "S1_3") (pintype "passive"))
    )
    (net (code "42") (name "unconnected-(IC1-PWRGD-Pad14)") (class "Default")
      (node (ref "IC1") (pin "14") (pinfunction "PWRGD_14") (pintype "passive"))
    )
    (net (code "43") (name "unconnected-(IC2-NC-Pad3)") (class "Default")
      (node (ref "IC2") (pin "3") (pinfunction "NC_3") (pintype "passive"))
    )
    (net (code "44") (name "unconnected-(IC7-SCL-Pad14)") (class "Default")
      (node (ref "IC7") (pin "14") (pinfunction "SCL_14") (pintype "passive+no_connect"))
    )
    (net (code "45") (name "unconnected-(IC7-SDA-Pad15)") (class "Default")
      (node (ref "IC7") (pin "15") (pinfunction "SDA_15") (pintype "passive+no_connect"))
    )
    (net (code "46") (name "unconnected-(IC7-~{ACOK}-Pad18)") (class "Default")
      (node (ref "IC7") (pin "18") (pinfunction "~{ACOK}_18") (pintype "passive+no_connect"))
    )
    (net (code "47") (name "unconnected-(SW1-Pad1)") (class "Default")
      (node (ref "SW1") (pin "1") (pinfunction "1_1") (pintype "passive"))
    )
    (net (code "48") (name "unconnected-(SW1-Pad4)") (class "Default")
      (node (ref "SW1") (pin "4") (pinfunction "4_4") (pintype "passive"))
    )
    (net (code "49") (name "unconnected-(SW1-Pad5)") (class "Default")
      (node (ref "SW1") (pin "5") (pinfunction "5_5") (pintype "passive"))
    )
    (net (code "50") (name "unconnected-(USB1-SUB1-PadA8)") (class "Default")
      (node (ref "USB1") (pin "A8") (pinfunction "SUB1_A8") (pintype "passive"))
    )
    (net (code "51") (name "unconnected-(USB1-SUB2-PadB8)") (class "Default")
      (node (ref "USB1") (pin "B8") (pinfunction "SUB2_B8") (pintype "passive"))
    )
  )
)
